# fan-regulator.net
KiCad netlist of a schematic drawn in Altium Designer
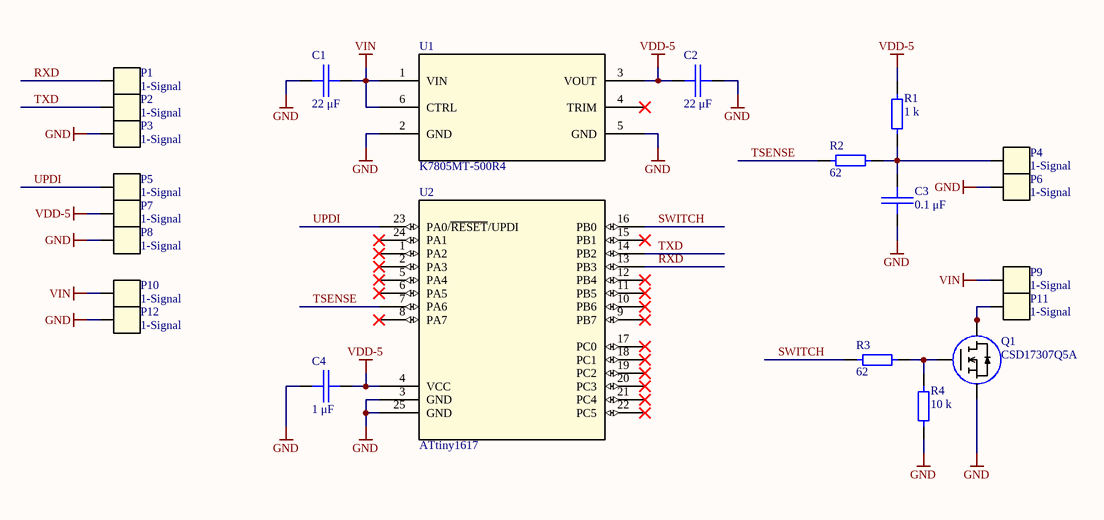
[diagram p0: fan-regulator.SchDoc]

(export (version "E")
  (design (tool "Eeschema 10.0.6"))
  (components
    (comp (ref "C1") (value "22 μF") (footprint "1210") (libsource (lib "AltiumDesigner") (part "Cap")))
    (comp (ref "C2") (value "22 μF") (footprint "1210") (libsource (lib "AltiumDesigner") (part "Cap")))
    (comp (ref "C3") (value "0.1 μF") (footprint "0603") (libsource (lib "AltiumDesigner") (part "Cap")))
    (comp (ref "C4") (value "1 μF") (footprint "0603") (libsource (lib "AltiumDesigner") (part "Cap")))
    (comp (ref "P1")
      (value "1-Signal")
      (footprint "1-SignalSmall")
      (libsource (lib "AltiumDesigner") (part "1-Signal"))
    )
    (comp (ref "P2")
      (value "1-Signal")
      (footprint "1-SignalSmall")
      (libsource (lib "AltiumDesigner") (part "1-Signal"))
    )
    (comp (ref "P3")
      (value "1-Signal")
      (footprint "1-SignalSmall")
      (libsource (lib "AltiumDesigner") (part "1-Signal"))
    )
    (comp (ref "P4")
      (value "1-Signal")
      (footprint "1-SignalSmall")
      (libsource (lib "AltiumDesigner") (part "1-Signal"))
    )
    (comp (ref "P5")
      (value "1-Signal")
      (footprint "1-SignalSmall")
      (libsource (lib "AltiumDesigner") (part "1-Signal"))
    )
    (comp (ref "P6")
      (value "1-Signal")
      (footprint "1-SignalSmall")
      (libsource (lib "AltiumDesigner") (part "1-Signal"))
    )
    (comp (ref "P7")
      (value "1-Signal")
      (footprint "1-SignalSmall")
      (libsource (lib "AltiumDesigner") (part "1-Signal"))
    )
    (comp (ref "P8")
      (value "1-Signal")
      (footprint "1-SignalSmall")
      (libsource (lib "AltiumDesigner") (part "1-Signal"))
    )
    (comp (ref "P9")
      (value "1-Signal")
      (footprint "1-SignalSmall")
      (libsource (lib "AltiumDesigner") (part "1-Signal"))
    )
    (comp (ref "P10")
      (value "1-Signal")
      (footprint "1-SignalSmall")
      (libsource (lib "AltiumDesigner") (part "1-Signal"))
    )
    (comp (ref "P11")
      (value "1-Signal")
      (footprint "1-SignalSmall")
      (libsource (lib "AltiumDesigner") (part "1-Signal"))
    )
    (comp (ref "P12")
      (value "1-Signal")
      (footprint "1-SignalSmall")
      (libsource (lib "AltiumDesigner") (part "1-Signal"))
    )
    (comp (ref "Q1")
      (value "CSD17307Q5A")
      (footprint "SON Q5A")
      (libsource (lib "AltiumDesigner") (part "CSD17307Q5A"))
    )
    (comp (ref "R1") (value "1 k") (footprint "0603") (libsource (lib "AltiumDesigner") (part "Res")))
    (comp (ref "R2") (value "62") (footprint "0603") (libsource (lib "AltiumDesigner") (part "Res")))
    (comp (ref "R3") (value "62") (footprint "0603") (libsource (lib "AltiumDesigner") (part "Res")))
    (comp (ref "R4") (value "10 k") (footprint "0603") (libsource (lib "AltiumDesigner") (part "Res")))
    (comp (ref "U1")
      (value "K7805MT-500R4")
      (footprint "K78xxMT-500R4")
      (libsource (lib "AltiumDesigner") (part "K78xxMT-500R4"))
    )
    (comp (ref "U2")
      (value "ATtiny1617")
      (footprint "VQFN24")
      (libsource (lib "AltiumDesigner") (part "ATtiny1617/3217"))
    )
  )
  (nets
    (net (code "1") (name "/RXD") (class "Default")
      (node (ref "P1") (pin "1") (pinfunction "1_1") (pintype "passive"))
      (node (ref "U2") (pin "13") (pinfunction "PB3_13") (pintype "bidirectional"))
    )
    (net (code "2") (name "/SWITCH") (class "Default")
      (node (ref "R3") (pin "1") (pinfunction "1_1") (pintype "passive"))
      (node (ref "U2") (pin "16") (pinfunction "PB0_16") (pintype "bidirectional"))
    )
    (net (code "3") (name "/TSENSE") (class "Default")
      (node (ref "R2") (pin "1") (pinfunction "1_1") (pintype "passive"))
      (node (ref "U2") (pin "7") (pinfunction "PA6_7") (pintype "bidirectional"))
    )
    (net (code "4") (name "/TXD") (class "Default")
      (node (ref "P2") (pin "1") (pinfunction "1_1") (pintype "passive"))
      (node (ref "U2") (pin "14") (pinfunction "PB2_14") (pintype "bidirectional"))
    )
    (net (code "5") (name "/UPDI") (class "Default")
      (node (ref "P5") (pin "1") (pinfunction "1_1") (pintype "passive"))
      (node (ref "U2") (pin "23") (pinfunction "PA0/~{RESET}/UPDI_23") (pintype "bidirectional"))
    )
    (net (code "6") (name "GND") (class "Default")
      (node (ref "C1") (pin "1") (pinfunction "1_1") (pintype "passive"))
      (node (ref "C2") (pin "2") (pinfunction "2_2") (pintype "passive"))
      (node (ref "C3") (pin "1") (pinfunction "1_1") (pintype "passive"))
      (node (ref "C4") (pin "2") (pinfunction "2_2") (pintype "passive"))
      (node (ref "P12") (pin "1") (pinfunction "1_1") (pintype "passive"))
      (node (ref "P3") (pin "1") (pinfunction "1_1") (pintype "passive"))
      (node (ref "P6") (pin "1") (pinfunction "1_1") (pintype "passive"))
      (node (ref "P8") (pin "1") (pinfunction "1_1") (pintype "passive"))
      (node (ref "Q1") (pin "1") (pinfunction "S_1") (pintype "passive"))
      (node (ref "Q1") (pin "2") (pinfunction "S_2") (pintype "passive"))
      (node (ref "Q1") (pin "3") (pinfunction "S_3") (pintype "passive"))
      (node (ref "R4") (pin "1") (pinfunction "1_1") (pintype "passive"))
      (node (ref "U1") (pin "2") (pinfunction "GND_2") (pintype "power_in"))
      (node (ref "U1") (pin "5") (pinfunction "GND_5") (pintype "power_in"))
      (node (ref "U2") (pin "25") (pinfunction "GND_25") (pintype "power_in"))
      (node (ref "U2") (pin "3") (pinfunction "GND_3") (pintype "power_in"))
    )
    (net (code "7") (name "Net-(C3-Pad2)") (class "Default")
      (node (ref "C3") (pin "2") (pinfunction "2_2") (pintype "passive"))
      (node (ref "P4") (pin "1") (pinfunction "1_1") (pintype "passive"))
      (node (ref "R1") (pin "1") (pinfunction "1_1") (pintype "passive"))
      (node (ref "R2") (pin "2") (pinfunction "2_2") (pintype "passive"))
    )
    (net (code "8") (name "Net-(P11-Pad1)") (class "Default")
      (node (ref "P11") (pin "1") (pinfunction "1_1") (pintype "passive"))
      (node (ref "Q1") (pin "5") (pinfunction "D_5") (pintype "passive"))
      (node (ref "Q1") (pin "6") (pinfunction "D_6") (pintype "passive"))
      (node (ref "Q1") (pin "7") (pinfunction "D_7") (pintype "passive"))
      (node (ref "Q1") (pin "8") (pinfunction "D_8") (pintype "passive"))
    )
    (net (code "9") (name "Net-(Q1-G)") (class "Default")
      (node (ref "Q1") (pin "4") (pinfunction "G_4") (pintype "passive"))
      (node (ref "R3") (pin "2") (pinfunction "2_2") (pintype "passive"))
      (node (ref "R4") (pin "2") (pinfunction "2_2") (pintype "passive"))
    )
    (net (code "10") (name "VDD-5") (class "Default")
      (node (ref "C2") (pin "1") (pinfunction "1_1") (pintype "passive"))
      (node (ref "C4") (pin "1") (pinfunction "1_1") (pintype "passive"))
      (node (ref "P7") (pin "1") (pinfunction "1_1") (pintype "passive"))
      (node (ref "R1") (pin "2") (pinfunction "2_2") (pintype "passive"))
      (node (ref "U1") (pin "3") (pinfunction "VOUT_3") (pintype "power_in"))
      (node (ref "U2") (pin "4") (pinfunction "VCC_4") (pintype "power_in"))
    )
    (net (code "11") (name "VIN") (class "Default")
      (node (ref "C1") (pin "2") (pinfunction "2_2") (pintype "passive"))
      (node (ref "P10") (pin "1") (pinfunction "1_1") (pintype "passive"))
      (node (ref "P9") (pin "1") (pinfunction "1_1") (pintype "passive"))
      (node (ref "U1") (pin "1") (pinfunction "VIN_1") (pintype "power_in"))
      (node (ref "U1") (pin "6") (pinfunction "CTRL_6") (pintype "passive"))
    )
    (net (code "12") (name "unconnected-(U1-TRIM-Pad4)") (class "Default")
      (node (ref "U1") (pin "4") (pinfunction "TRIM_4") (pintype "passive+no_connect"))
    )
    (net (code "13") (name "unconnected-(U2-PA1-Pad24)") (class "Default")
      (node (ref "U2") (pin "24") (pinfunction "PA1_24") (pintype "bidirectional+no_connect"))
    )
    (net (code "14") (name "unconnected-(U2-PA2-Pad1)") (class "Default")
      (node (ref "U2") (pin "1") (pinfunction "PA2_1") (pintype "bidirectional+no_connect"))
    )
    (net (code "15") (name "unconnected-(U2-PA3-Pad2)") (class "Default")
      (node (ref "U2") (pin "2") (pinfunction "PA3_2") (pintype "bidirectional+no_connect"))
    )
    (net (code "16") (name "unconnected-(U2-PA4-Pad5)") (class "Default")
      (node (ref "U2") (pin "5") (pinfunction "PA4_5") (pintype "bidirectional+no_connect"))
    )
    (net (code "17") (name "unconnected-(U2-PA5-Pad6)") (class "Default")
      (node (ref "U2") (pin "6") (pinfunction "PA5_6") (pintype "bidirectional+no_connect"))
    )
    (net (code "18") (name "unconnected-(U2-PA7-Pad8)") (class "Default")
      (node (ref "U2") (pin "8") (pinfunction "PA7_8") (pintype "bidirectional+no_connect"))
    )
    (net (code "19") (name "unconnected-(U2-PB1-Pad15)") (class "Default")
      (node (ref "U2") (pin "15") (pinfunction "PB1_15") (pintype "bidirectional+no_connect"))
    )
    (net (code "20") (name "unconnected-(U2-PB4-Pad12)") (class "Default")
      (node (ref "U2") (pin "12") (pinfunction "PB4_12") (pintype "bidirectional+no_connect"))
    )
    (net (code "21") (name "unconnected-(U2-PB5-Pad11)") (class "Default")
      (node (ref "U2") (pin "11") (pinfunction "PB5_11") (pintype "bidirectional+no_connect"))
    )
    (net (code "22") (name "unconnected-(U2-PB6-Pad10)") (class "Default")
      (node (ref "U2") (pin "10") (pinfunction "PB6_10") (pintype "bidirectional+no_connect"))
    )
    (net (code "23") (name "unconnected-(U2-PB7-Pad9)") (class "Default")
      (node (ref "U2") (pin "9") (pinfunction "PB7_9") (pintype "bidirectional+no_connect"))
    )
    (net (code "24") (name "unconnected-(U2-PC0-Pad17)") (class "Default")
      (node (ref "U2") (pin "17") (pinfunction "PC0_17") (pintype "bidirectional+no_connect"))
    )
    (net (code "25") (name "unconnected-(U2-PC1-Pad18)") (class "Default")
      (node (ref "U2") (pin "18") (pinfunction "PC1_18") (pintype "bidirectional+no_connect"))
    )
    (net (code "26") (name "unconnected-(U2-PC2-Pad19)") (class "Default")
      (node (ref "U2") (pin "19") (pinfunction "PC2_19") (pintype "bidirectional+no_connect"))
    )
    (net (code "27") (name "unconnected-(U2-PC3-Pad20)") (class "Default")
      (node (ref "U2") (pin "20") (pinfunction "PC3_20") (pintype "bidirectional+no_connect"))
    )
    (net (code "28") (name "unconnected-(U2-PC4-Pad21)") (class "Default")
      (node (ref "U2") (pin "21") (pinfunction "PC4_21") (pintype "bidirectional+no_connect"))
    )
    (net (code "29") (name "unconnected-(U2-PC5-Pad22)") (class "Default")
      (node (ref "U2") (pin "22") (pinfunction "PC5_22") (pintype "bidirectional+no_connect"))
    )
  )
)
